# simon_game.net
KiCad netlist of a schematic drawn in EAGLE
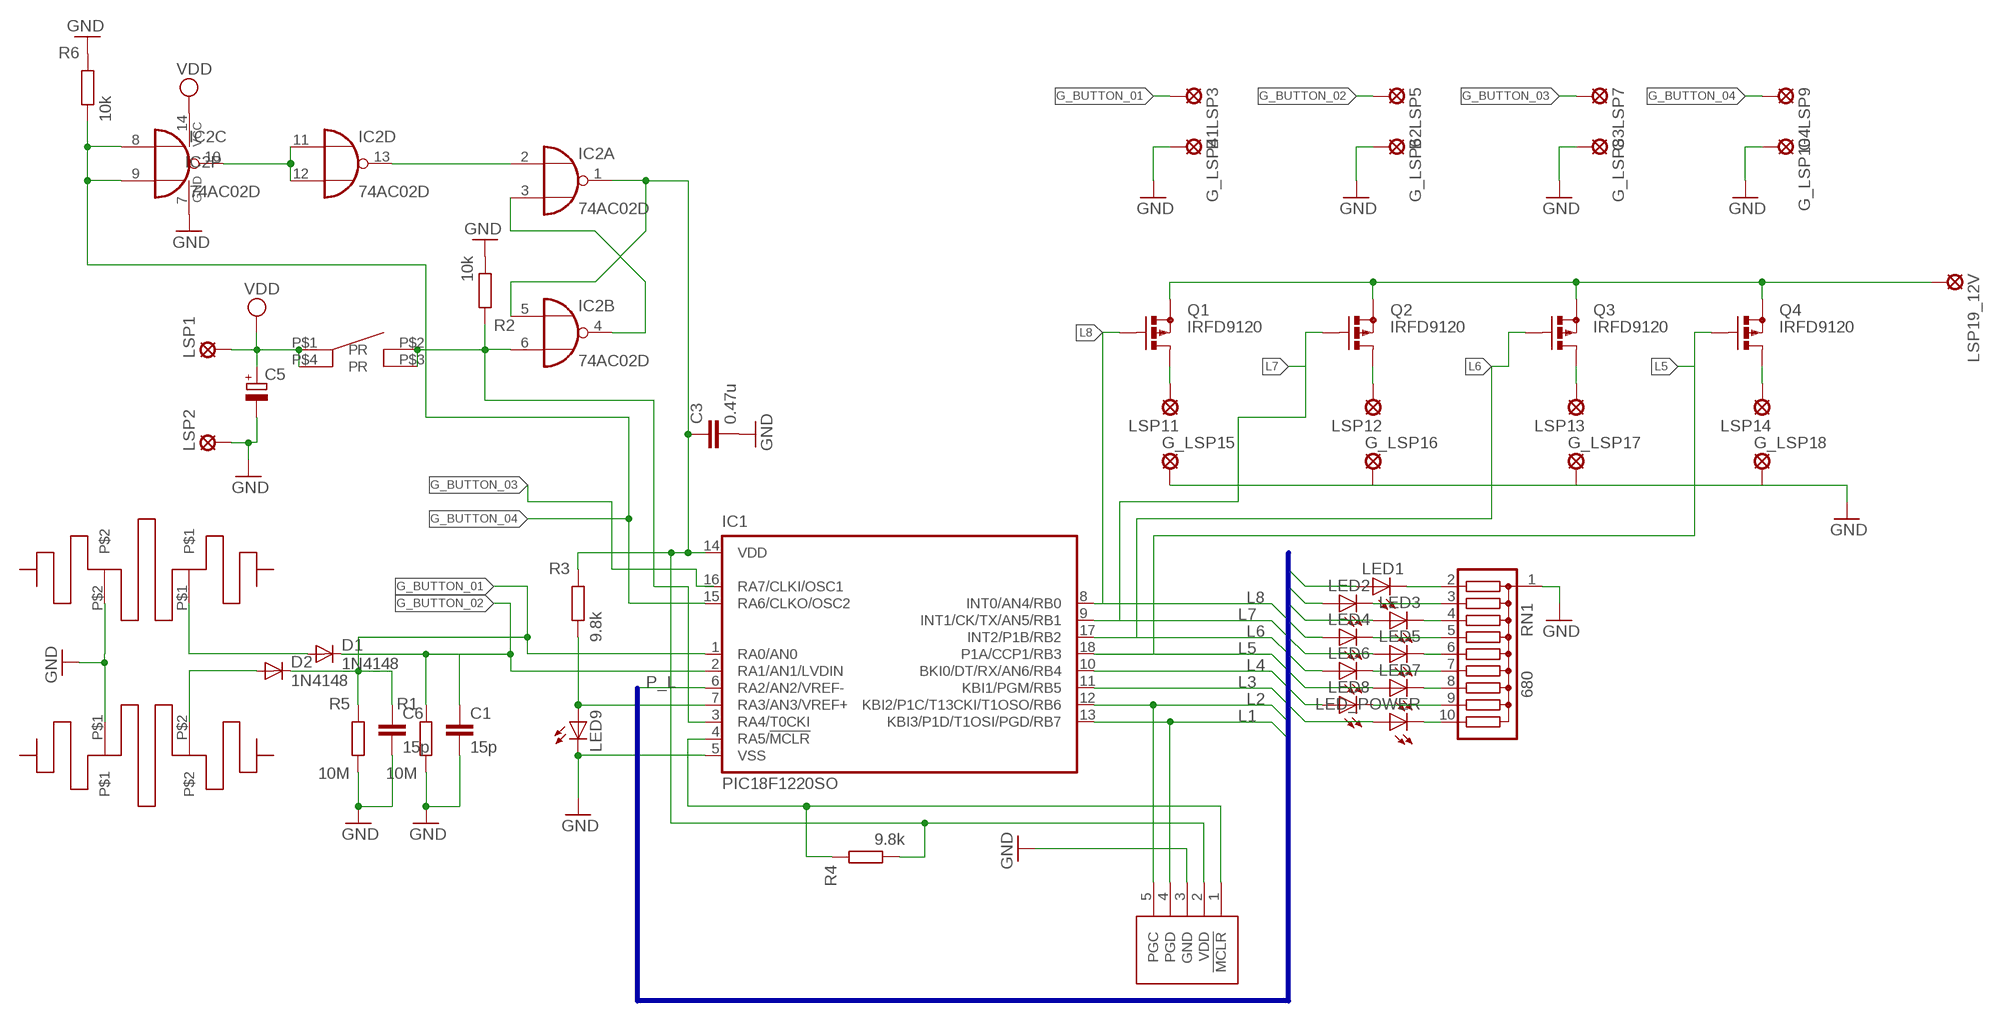
[diagram p0: schematic, sheet 1]

(export (version "E")
  (design (tool "Eeschema 10.0.6"))
  (components
    (comp (ref "B1LSP3")
      (value "SE14")
      (footprint "eagle-import:SE14")
      (libsource (lib "eagle-import") (part "SE14"))
    )
    (comp (ref "B2LSP5")
      (value "SE14")
      (footprint "eagle-import:SE14")
      (libsource (lib "eagle-import") (part "SE14"))
    )
    (comp (ref "C1")
      (value "15p")
      (footprint "eagle-import:C1206")
      (libsource (lib "eagle-import") (part "C-EUC1206"))
    )
    (comp (ref "C3")
      (value "0.47u")
      (footprint "eagle-import:C1206")
      (libsource (lib "eagle-import") (part "C-EUC1206"))
    )
    (comp (ref "C5")
      (value "CPOL-EUSMCA")
      (footprint "eagle-import:SMC_A")
      (libsource (lib "eagle-import") (part "CPOL-EUSMCA"))
    )
    (comp (ref "C6")
      (value "15p")
      (footprint "eagle-import:C1206")
      (libsource (lib "eagle-import") (part "C-EUC1206"))
    )
    (comp (ref "D1")
      (value "1N4148")
      (footprint "eagle-import:DO35-10")
      (libsource (lib "eagle-import") (part "1N4148"))
    )
    (comp (ref "D2")
      (value "1N4148")
      (footprint "eagle-import:DO35-10")
      (libsource (lib "eagle-import") (part "1N4148"))
    )
    (comp (ref "G3LSP7")
      (value "SE14")
      (footprint "eagle-import:SE14")
      (libsource (lib "eagle-import") (part "SE14"))
    )
    (comp (ref "G4LSP9")
      (value "SE14")
      (footprint "eagle-import:SE14")
      (libsource (lib "eagle-import") (part "SE14"))
    )
    (comp (ref "G_LSP4")
      (value "SE14")
      (footprint "eagle-import:SE14")
      (libsource (lib "eagle-import") (part "SE14"))
    )
    (comp (ref "G_LSP6")
      (value "SE14")
      (footprint "eagle-import:SE14")
      (libsource (lib "eagle-import") (part "SE14"))
    )
    (comp (ref "G_LSP8")
      (value "SE14")
      (footprint "eagle-import:SE14")
      (libsource (lib "eagle-import") (part "SE14"))
    )
    (comp (ref "G_LSP10")
      (value "SE14")
      (footprint "eagle-import:SE14")
      (libsource (lib "eagle-import") (part "SE14"))
    )
    (comp (ref "G_LSP15")
      (value "SE14")
      (footprint "eagle-import:SE14")
      (libsource (lib "eagle-import") (part "SE14"))
    )
    (comp (ref "G_LSP16")
      (value "SE14")
      (footprint "eagle-import:SE14")
      (libsource (lib "eagle-import") (part "SE14"))
    )
    (comp (ref "G_LSP17")
      (value "SE14")
      (footprint "eagle-import:SE14")
      (libsource (lib "eagle-import") (part "SE14"))
    )
    (comp (ref "G_LSP18")
      (value "SE14")
      (footprint "eagle-import:SE14")
      (libsource (lib "eagle-import") (part "SE14"))
    )
    (comp (ref "IC1")
      (value "PIC18F1220SO")
      (footprint "eagle-import:SO-18W")
      (libsource (lib "eagle-import") (part "PIC18F120SO2"))
    )
    (comp (ref "IC2")
      (value "74AC02D")
      (footprint "eagle-import:SO14")
      (libsource (lib "eagle-import") (part "7402DAC"))
    )
    (comp (ref "LED1")
      (value "LED3MM")
      (footprint "eagle-import:LED3MM")
      (libsource (lib "eagle-import") (part "LED3MM"))
    )
    (comp (ref "LED2")
      (value "LED3MM")
      (footprint "eagle-import:LED3MM")
      (libsource (lib "eagle-import") (part "LED3MM"))
    )
    (comp (ref "LED3")
      (value "LED3MM")
      (footprint "eagle-import:LED3MM")
      (libsource (lib "eagle-import") (part "LED3MM"))
    )
    (comp (ref "LED4")
      (value "LED3MM")
      (footprint "eagle-import:LED3MM")
      (libsource (lib "eagle-import") (part "LED3MM"))
    )
    (comp (ref "LED5")
      (value "LED3MM")
      (footprint "eagle-import:LED3MM")
      (libsource (lib "eagle-import") (part "LED3MM"))
    )
    (comp (ref "LED6")
      (value "LED3MM")
      (footprint "eagle-import:LED3MM")
      (libsource (lib "eagle-import") (part "LED3MM"))
    )
    (comp (ref "LED7")
      (value "LED3MM")
      (footprint "eagle-import:LED3MM")
      (libsource (lib "eagle-import") (part "LED3MM"))
    )
    (comp (ref "LED8")
      (value "LED3MM")
      (footprint "eagle-import:LED3MM")
      (libsource (lib "eagle-import") (part "LED3MM"))
    )
    (comp (ref "LED9")
      (value "LED5MM")
      (footprint "eagle-import:LED5MM")
      (libsource (lib "eagle-import") (part "LED5MM"))
    )
    (comp (ref "LED_POWER")
      (value "LED3MM")
      (footprint "eagle-import:LED3MM")
      (libsource (lib "eagle-import") (part "LED3MM"))
    )
    (comp (ref "LSP1")
      (value "SE14")
      (footprint "eagle-import:SE14")
      (libsource (lib "eagle-import") (part "SE14"))
    )
    (comp (ref "LSP2")
      (value "SE14")
      (footprint "eagle-import:SE14")
      (libsource (lib "eagle-import") (part "SE14"))
    )
    (comp (ref "LSP11")
      (value "SE14")
      (footprint "eagle-import:SE14")
      (libsource (lib "eagle-import") (part "SE14"))
    )
    (comp (ref "LSP12")
      (value "SE14")
      (footprint "eagle-import:SE14")
      (libsource (lib "eagle-import") (part "SE14"))
    )
    (comp (ref "LSP13")
      (value "SE14")
      (footprint "eagle-import:SE14")
      (libsource (lib "eagle-import") (part "SE14"))
    )
    (comp (ref "LSP14")
      (value "SE14")
      (footprint "eagle-import:SE14")
      (libsource (lib "eagle-import") (part "SE14"))
    )
    (comp (ref "LSP19_12V")
      (value "SE14")
      (footprint "eagle-import:SE14")
      (libsource (lib "eagle-import") (part "SE14"))
    )
    (comp (ref "Q1")
      (value "IRFD9120")
      (footprint "eagle-import:C370-01")
      (libsource (lib "eagle-import") (part "IRFD9120"))
    )
    (comp (ref "Q2")
      (value "IRFD9120")
      (footprint "eagle-import:C370-01")
      (libsource (lib "eagle-import") (part "IRFD9120"))
    )
    (comp (ref "Q3")
      (value "IRFD9120")
      (footprint "eagle-import:C370-01")
      (libsource (lib "eagle-import") (part "IRFD9120"))
    )
    (comp (ref "Q4")
      (value "IRFD9120")
      (footprint "eagle-import:C370-01")
      (libsource (lib "eagle-import") (part "IRFD9120"))
    )
    (comp (ref "R1")
      (value "10M")
      (footprint "eagle-import:M1206")
      (libsource (lib "eagle-import") (part "R-EU_M1206"))
    )
    (comp (ref "R2")
      (value "10k")
      (footprint "eagle-import:M1206")
      (libsource (lib "eagle-import") (part "R-EU_M1206"))
    )
    (comp (ref "R3")
      (value "9.8k")
      (footprint "eagle-import:M1206")
      (libsource (lib "eagle-import") (part "R-EU_M1206"))
    )
    (comp (ref "R4")
      (value "9.8k")
      (footprint "eagle-import:M1206")
      (libsource (lib "eagle-import") (part "R-EU_M1206"))
    )
    (comp (ref "R5")
      (value "10M")
      (footprint "eagle-import:M1206")
      (libsource (lib "eagle-import") (part "R-EU_M1206"))
    )
    (comp (ref "R6")
      (value "10k")
      (footprint "eagle-import:M1206")
      (libsource (lib "eagle-import") (part "R-EU_M1206"))
    )
    (comp (ref "RN1")
      (value "680")
      (footprint "eagle-import:SIL10")
      (libsource (lib "eagle-import") (part "G09R"))
    )
    (comp (ref "U$1")
      (value "TIKBUTTON01")
      (footprint "eagle-import:TIKBUTTON01")
      (libsource (lib "eagle-import") (part "TIKBUTTON01"))
    )
    (comp (ref "U$2")
      (value "ANTENNA")
      (footprint "eagle-import:ANT!")
      (libsource (lib "eagle-import") (part "ANTENNA"))
    )
    (comp (ref "U$3")
      (value "ANTENNA")
      (footprint "eagle-import:ANT!")
      (libsource (lib "eagle-import") (part "ANTENNA"))
    )
    (comp (ref "U$4")
      (value "PIC-PROG-CON")
      (footprint "eagle-import:PIC-PROG-CON")
      (libsource (lib "eagle-import") (part "PIC-PROG-CON"))
    )
  )
  (nets
    (net (code "1") (name "/L1") (class "Default")
      (node (ref "IC1") (pin "13") (pinfunction "KBI3/P1D/T1OSI/PGD/RB7_13") (pintype "bidirectional"))
      (node (ref "LED1") (pin "A") (pinfunction "A_A") (pintype "passive"))
      (node (ref "U$4") (pin "4") (pinfunction "PGD_4") (pintype "bidirectional"))
    )
    (net (code "2") (name "/L2") (class "Default")
      (node (ref "IC1") (pin "12") (pinfunction "KBI2/P1C/T13CKI/T1OSO/RB6_12") (pintype "bidirectional"))
      (node (ref "LED2") (pin "A") (pinfunction "A_A") (pintype "passive"))
      (node (ref "U$4") (pin "5") (pinfunction "PGC_5") (pintype "bidirectional"))
    )
    (net (code "3") (name "/L3") (class "Default")
      (node (ref "IC1") (pin "11") (pinfunction "KBI1/PGM/RB5_11") (pintype "bidirectional"))
      (node (ref "LED3") (pin "A") (pinfunction "A_A") (pintype "passive"))
    )
    (net (code "4") (name "/L4") (class "Default")
      (node (ref "IC1") (pin "10") (pinfunction "BKI0/DT/RX/AN6/RB4_10") (pintype "bidirectional"))
      (node (ref "LED4") (pin "A") (pinfunction "A_A") (pintype "passive"))
    )
    (net (code "5") (name "/P_L") (class "Default")
      (node (ref "IC1") (pin "6") (pinfunction "RA2/AN2/VREF-_6") (pintype "bidirectional"))
      (node (ref "LED_POWER") (pin "A") (pinfunction "A_A") (pintype "passive"))
    )
    (net (code "6") (name "GND") (class "Default")
      (node (ref "C1") (pin "2") (pinfunction "2_2") (pintype "passive"))
      (node (ref "C3") (pin "2") (pinfunction "2_2") (pintype "passive"))
      (node (ref "C5") (pin "-") (pinfunction "-_-") (pintype "passive"))
      (node (ref "C6") (pin "2") (pinfunction "2_2") (pintype "passive"))
      (node (ref "G_LSP10") (pin "MP") (pinfunction "MP_MP") (pintype "passive"))
      (node (ref "G_LSP15") (pin "MP") (pinfunction "MP_MP") (pintype "passive"))
      (node (ref "G_LSP16") (pin "MP") (pinfunction "MP_MP") (pintype "passive"))
      (node (ref "G_LSP17") (pin "MP") (pinfunction "MP_MP") (pintype "passive"))
      (node (ref "G_LSP18") (pin "MP") (pinfunction "MP_MP") (pintype "passive"))
      (node (ref "G_LSP4") (pin "MP") (pinfunction "MP_MP") (pintype "passive"))
      (node (ref "G_LSP6") (pin "MP") (pinfunction "MP_MP") (pintype "passive"))
      (node (ref "G_LSP8") (pin "MP") (pinfunction "MP_MP") (pintype "passive"))
      (node (ref "IC1") (pin "5") (pinfunction "VSS_5") (pintype "power_in"))
      (node (ref "IC2") (pin "7") (pinfunction "GND_7") (pintype "power_in"))
      (node (ref "LED9") (pin "K") (pinfunction "C_K") (pintype "passive"))
      (node (ref "LSP2") (pin "MP") (pinfunction "MP_MP") (pintype "passive"))
      (node (ref "R1") (pin "1") (pinfunction "1_1") (pintype "passive"))
      (node (ref "R2") (pin "1") (pinfunction "1_1") (pintype "passive"))
      (node (ref "R5") (pin "1") (pinfunction "1_1") (pintype "passive"))
      (node (ref "R6") (pin "2") (pinfunction "2_2") (pintype "passive"))
      (node (ref "RN1") (pin "1") (pinfunction "1_1") (pintype "passive"))
      (node (ref "U$2") (pin "P$1") (pinfunction "P$1_P$1") (pintype "bidirectional"))
      (node (ref "U$3") (pin "P$2") (pinfunction "P$2_P$2") (pintype "bidirectional"))
      (node (ref "U$4") (pin "3") (pinfunction "GND_3") (pintype "bidirectional"))
    )
    (net (code "7") (name "G_BUTTON_01") (class "Default")
      (node (ref "B1LSP3") (pin "MP") (pinfunction "MP_MP") (pintype "passive"))
      (node (ref "C6") (pin "1") (pinfunction "1_1") (pintype "passive"))
      (node (ref "D2") (pin "C") (pinfunction "C_C") (pintype "passive"))
      (node (ref "IC1") (pin "1") (pinfunction "RA0/AN0_1") (pintype "bidirectional"))
      (node (ref "R5") (pin "2") (pinfunction "2_2") (pintype "passive"))
    )
    (net (code "8") (name "G_BUTTON_02") (class "Default")
      (node (ref "B2LSP5") (pin "MP") (pinfunction "MP_MP") (pintype "passive"))
      (node (ref "C1") (pin "1") (pinfunction "1_1") (pintype "passive"))
      (node (ref "D1") (pin "C") (pinfunction "C_C") (pintype "passive"))
      (node (ref "IC1") (pin "2") (pinfunction "RA1/AN1/LVDIN_2") (pintype "bidirectional"))
      (node (ref "R1") (pin "2") (pinfunction "2_2") (pintype "passive"))
    )
    (net (code "9") (name "G_BUTTON_03") (class "Default")
      (node (ref "G3LSP7") (pin "MP") (pinfunction "MP_MP") (pintype "passive"))
    )
    (net (code "10") (name "G_BUTTON_04") (class "Default")
      (node (ref "G4LSP9") (pin "MP") (pinfunction "MP_MP") (pintype "passive"))
      (node (ref "IC1") (pin "15") (pinfunction "RA6/CLKO/OSC2_15") (pintype "bidirectional"))
      (node (ref "IC2") (pin "8") (pinfunction "I0_8") (pintype "input"))
      (node (ref "IC2") (pin "9") (pinfunction "I1_9") (pintype "input"))
      (node (ref "R6") (pin "1") (pinfunction "1_1") (pintype "passive"))
    )
    (net (code "11") (name "L5") (class "Default")
      (node (ref "IC1") (pin "18") (pinfunction "P1A/CCP1/RB3_18") (pintype "bidirectional"))
      (node (ref "LED5") (pin "A") (pinfunction "A_A") (pintype "passive"))
      (node (ref "Q4") (pin "G") (pinfunction "G_G") (pintype "passive"))
    )
    (net (code "12") (name "L6") (class "Default")
      (node (ref "IC1") (pin "17") (pinfunction "INT2/P1B/RB2_17") (pintype "bidirectional"))
      (node (ref "LED6") (pin "A") (pinfunction "A_A") (pintype "passive"))
      (node (ref "Q3") (pin "G") (pinfunction "G_G") (pintype "passive"))
    )
    (net (code "13") (name "L7") (class "Default")
      (node (ref "IC1") (pin "9") (pinfunction "INT1/CK/TX/AN5/RB1_9") (pintype "bidirectional"))
      (node (ref "LED7") (pin "A") (pinfunction "A_A") (pintype "passive"))
      (node (ref "Q2") (pin "G") (pinfunction "G_G") (pintype "passive"))
    )
    (net (code "14") (name "L8") (class "Default")
      (node (ref "IC1") (pin "8") (pinfunction "INT0/AN4/RB0_8") (pintype "bidirectional"))
      (node (ref "LED8") (pin "A") (pinfunction "A_A") (pintype "passive"))
      (node (ref "Q1") (pin "G") (pinfunction "G_G") (pintype "passive"))
    )
    (net (code "15") (name "Net-(D1-PadA)") (class "Default")
      (node (ref "D1") (pin "A") (pinfunction "A_A") (pintype "passive"))
      (node (ref "U$3") (pin "P$1") (pinfunction "P$1_P$1") (pintype "bidirectional"))
    )
    (net (code "16") (name "Net-(D2-PadA)") (class "Default")
      (node (ref "D2") (pin "A") (pinfunction "A_A") (pintype "passive"))
      (node (ref "U$2") (pin "P$2") (pinfunction "P$2_P$2") (pintype "bidirectional"))
    )
    (net (code "17") (name "Net-(IC1-RA3{slash}AN3{slash}VREF+)") (class "Default")
      (node (ref "IC1") (pin "7") (pinfunction "RA3/AN3/VREF+_7") (pintype "bidirectional"))
      (node (ref "LED9") (pin "A") (pinfunction "A_A") (pintype "passive"))
      (node (ref "R3") (pin "1") (pinfunction "1_1") (pintype "passive"))
    )
    (net (code "18") (name "Net-(IC1-RA4{slash}T0CKI)") (class "Default")
      (node (ref "IC1") (pin "3") (pinfunction "RA4/T0CKI_3") (pintype "bidirectional"))
      (node (ref "IC2") (pin "6") (pinfunction "I1_6") (pintype "input"))
      (node (ref "R2") (pin "2") (pinfunction "2_2") (pintype "passive"))
      (node (ref "U$1") (pin "P$2") (pinfunction "R_P$2") (pintype "output"))
      (node (ref "U$1") (pin "P$3") (pinfunction "R_P$3") (pintype "bidirectional"))
    )
    (net (code "19") (name "Net-(IC1-RA5{slash}~{MCLR})") (class "Default")
      (node (ref "IC1") (pin "4") (pinfunction "RA5/~{MCLR}_4") (pintype "input"))
      (node (ref "R4") (pin "2") (pinfunction "2_2") (pintype "passive"))
      (node (ref "U$4") (pin "1") (pinfunction "~{MCLR}_1") (pintype "bidirectional"))
    )
    (net (code "20") (name "Net-(IC1-VDD)") (class "Default")
      (node (ref "C3") (pin "1") (pinfunction "1_1") (pintype "passive"))
      (node (ref "IC1") (pin "14") (pinfunction "VDD_14") (pintype "power_in"))
      (node (ref "IC2") (pin "1") (pinfunction "O_1") (pintype "output"))
      (node (ref "IC2") (pin "5") (pinfunction "I0_5") (pintype "input"))
      (node (ref "R3") (pin "2") (pinfunction "2_2") (pintype "passive"))
      (node (ref "R4") (pin "1") (pinfunction "1_1") (pintype "passive"))
      (node (ref "U$4") (pin "2") (pinfunction "VDD_2") (pintype "bidirectional"))
    )
    (net (code "21") (name "Net-(IC2A-I0)") (class "Default")
      (node (ref "IC2") (pin "13") (pinfunction "O_13") (pintype "output"))
      (node (ref "IC2") (pin "2") (pinfunction "I0_2") (pintype "input"))
    )
    (net (code "22") (name "Net-(IC2A-I1)") (class "Default")
      (node (ref "IC2") (pin "3") (pinfunction "I1_3") (pintype "input"))
      (node (ref "IC2") (pin "4") (pinfunction "O_4") (pintype "output"))
    )
    (net (code "23") (name "Net-(IC2C-O)") (class "Default")
      (node (ref "IC2") (pin "10") (pinfunction "O_10") (pintype "output"))
      (node (ref "IC2") (pin "11") (pinfunction "I0_11") (pintype "input"))
      (node (ref "IC2") (pin "12") (pinfunction "I1_12") (pintype "input"))
    )
    (net (code "24") (name "Net-(LED1-C)") (class "Default")
      (node (ref "LED1") (pin "K") (pinfunction "C_K") (pintype "passive"))
      (node (ref "RN1") (pin "2") (pinfunction "2_2") (pintype "passive"))
    )
    (net (code "25") (name "Net-(LED2-C)") (class "Default")
      (node (ref "LED2") (pin "K") (pinfunction "C_K") (pintype "passive"))
      (node (ref "RN1") (pin "3") (pinfunction "3_3") (pintype "passive"))
    )
    (net (code "26") (name "Net-(LED3-C)") (class "Default")
      (node (ref "LED3") (pin "K") (pinfunction "C_K") (pintype "passive"))
      (node (ref "RN1") (pin "4") (pinfunction "4_4") (pintype "passive"))
    )
    (net (code "27") (name "Net-(LED4-C)") (class "Default")
      (node (ref "LED4") (pin "K") (pinfunction "C_K") (pintype "passive"))
      (node (ref "RN1") (pin "5") (pinfunction "5_5") (pintype "passive"))
    )
    (net (code "28") (name "Net-(LED5-C)") (class "Default")
      (node (ref "LED5") (pin "K") (pinfunction "C_K") (pintype "passive"))
      (node (ref "RN1") (pin "6") (pinfunction "6_6") (pintype "passive"))
    )
    (net (code "29") (name "Net-(LED6-C)") (class "Default")
      (node (ref "LED6") (pin "K") (pinfunction "C_K") (pintype "passive"))
      (node (ref "RN1") (pin "7") (pinfunction "7_7") (pintype "passive"))
    )
    (net (code "30") (name "Net-(LED7-C)") (class "Default")
      (node (ref "LED7") (pin "K") (pinfunction "C_K") (pintype "passive"))
      (node (ref "RN1") (pin "8") (pinfunction "8_8") (pintype "passive"))
    )
    (net (code "31") (name "Net-(LED8-C)") (class "Default")
      (node (ref "LED8") (pin "K") (pinfunction "C_K") (pintype "passive"))
      (node (ref "RN1") (pin "9") (pinfunction "9_9") (pintype "passive"))
    )
    (net (code "32") (name "Net-(LED_POWER-C)") (class "Default")
      (node (ref "LED_POWER") (pin "K") (pinfunction "C_K") (pintype "passive"))
      (node (ref "RN1") (pin "10") (pinfunction "10_10") (pintype "passive"))
    )
    (net (code "33") (name "Net-(LSP11-PadMP)") (class "Default")
      (node (ref "LSP11") (pin "MP") (pinfunction "MP_MP") (pintype "passive"))
      (node (ref "Q1") (pin "D") (pinfunction "D_D") (pintype "passive"))
      (node (ref "Q1") (pin "D1") (pinfunction "D_D1") (pintype "passive"))
    )
    (net (code "34") (name "Net-(LSP12-PadMP)") (class "Default")
      (node (ref "LSP12") (pin "MP") (pinfunction "MP_MP") (pintype "passive"))
      (node (ref "Q2") (pin "D") (pinfunction "D_D") (pintype "passive"))
      (node (ref "Q2") (pin "D1") (pinfunction "D_D1") (pintype "passive"))
    )
    (net (code "35") (name "Net-(LSP13-PadMP)") (class "Default")
      (node (ref "LSP13") (pin "MP") (pinfunction "MP_MP") (pintype "passive"))
      (node (ref "Q3") (pin "D") (pinfunction "D_D") (pintype "passive"))
      (node (ref "Q3") (pin "D1") (pinfunction "D_D1") (pintype "passive"))
    )
    (net (code "36") (name "Net-(LSP14-PadMP)") (class "Default")
      (node (ref "LSP14") (pin "MP") (pinfunction "MP_MP") (pintype "passive"))
      (node (ref "Q4") (pin "D") (pinfunction "D_D") (pintype "passive"))
      (node (ref "Q4") (pin "D1") (pinfunction "D_D1") (pintype "passive"))
    )
    (net (code "37") (name "Net-(LSP19_12V-PadMP)") (class "Default")
      (node (ref "LSP19_12V") (pin "MP") (pinfunction "MP_MP") (pintype "passive"))
      (node (ref "Q1") (pin "S") (pinfunction "S_S") (pintype "passive"))
      (node (ref "Q2") (pin "S") (pinfunction "S_S") (pintype "passive"))
      (node (ref "Q3") (pin "S") (pinfunction "S_S") (pintype "passive"))
      (node (ref "Q4") (pin "S") (pinfunction "S_S") (pintype "passive"))
    )
    (net (code "38") (name "VDD") (class "Default")
      (node (ref "C5") (pin "+") (pinfunction "+_+") (pintype "passive"))
      (node (ref "IC2") (pin "14") (pinfunction "VCC_14") (pintype "power_in"))
      (node (ref "LSP1") (pin "MP") (pinfunction "MP_MP") (pintype "passive"))
      (node (ref "U$1") (pin "P$1") (pinfunction "P_P$1") (pintype "input"))
      (node (ref "U$1") (pin "P$4") (pinfunction "P_P$4") (pintype "bidirectional"))
    )
    (net (code "39") (name "unconnected-(IC1-RA7{slash}CLKI{slash}OSC1-Pad16)") (class "Default")
      (node (ref "IC1") (pin "16") (pinfunction "RA7/CLKI/OSC1_16") (pintype "bidirectional"))
    )
  )
)
